# Kappa_R1.net
KiCad netlist of a schematic drawn in EAGLE
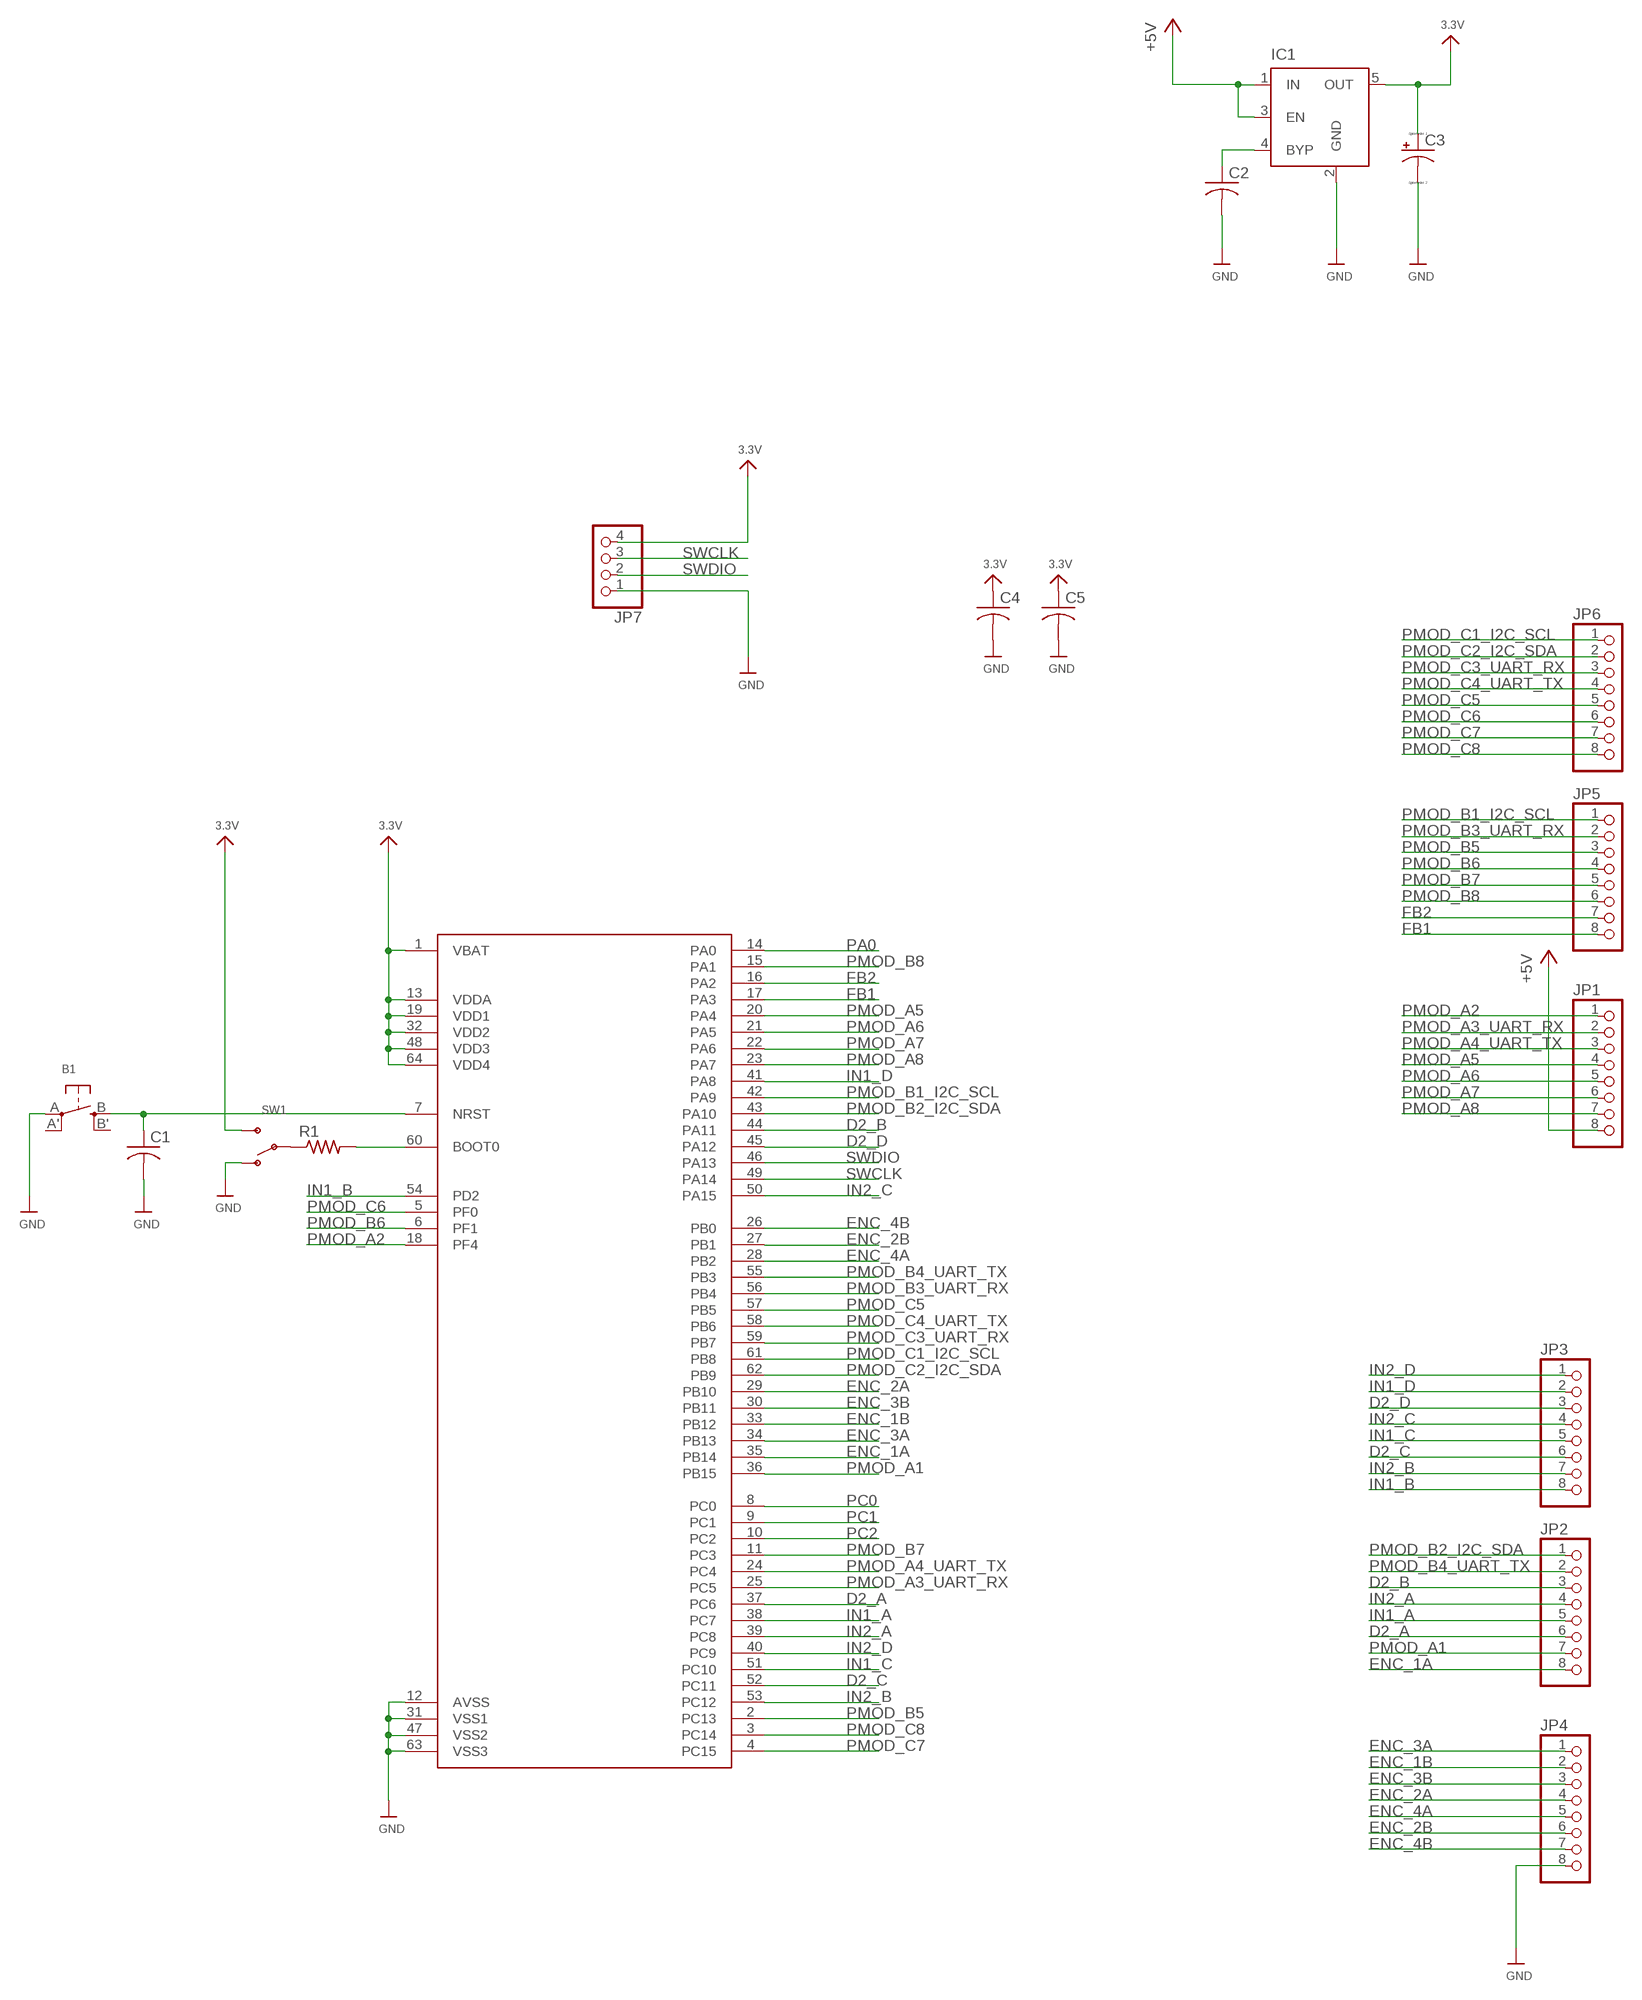
[diagram p0: schematic, sheet 1]

(export (version "E")
  (design (tool "Eeschema 10.0.6"))
  (components
    (comp (ref "B1")
      (value "SWITCH_TACT_SMT4.6X2.8")
      (footprint "eagle-import:BTN_KMR2_4.6X2.8")
      (libsource (lib "eagle-import") (part "SWITCH_TACT_SMT4.6X2.8"))
    )
    (comp (ref "C1")
      (value "C-USC0805K")
      (footprint "eagle-import:C0805K")
      (libsource (lib "eagle-import") (part "C-USC0805K"))
    )
    (comp (ref "C2")
      (value "C-USC0805K")
      (footprint "eagle-import:C0805K")
      (libsource (lib "eagle-import") (part "C-USC0805K"))
    )
    (comp (ref "C3")
      (value "CPOL-USCT3216")
      (footprint "eagle-import:CT3216")
      (libsource (lib "eagle-import") (part "CPOL-USCT3216"))
    )
    (comp (ref "C4")
      (value "C-USC0805")
      (footprint "eagle-import:C0805")
      (libsource (lib "eagle-import") (part "C-USC0805"))
    )
    (comp (ref "C5")
      (value "C-USC0805")
      (footprint "eagle-import:C0805")
      (libsource (lib "eagle-import") (part "C-USC0805"))
    )
    (comp (ref "IC1")
      (value "MIC5219XX")
      (footprint "eagle-import:SOT23-5")
      (libsource (lib "eagle-import") (part "MIC5219XX"))
    )
    (comp (ref "JP1")
      (value "HEADER-1X8ROUND")
      (footprint "eagle-import:1X08_ROUND")
      (libsource (lib "eagle-import") (part "HEADER-1X8ROUND"))
    )
    (comp (ref "JP2")
      (value "HEADER-1X8ROUND")
      (footprint "eagle-import:1X08_ROUND")
      (libsource (lib "eagle-import") (part "HEADER-1X8ROUND"))
    )
    (comp (ref "JP3")
      (value "HEADER-1X8ROUND")
      (footprint "eagle-import:1X08_ROUND")
      (libsource (lib "eagle-import") (part "HEADER-1X8ROUND"))
    )
    (comp (ref "JP4")
      (value "HEADER-1X8ROUND")
      (footprint "eagle-import:1X08_ROUND")
      (libsource (lib "eagle-import") (part "HEADER-1X8ROUND"))
    )
    (comp (ref "JP5")
      (value "HEADER-1X8ROUND")
      (footprint "eagle-import:1X08_ROUND")
      (libsource (lib "eagle-import") (part "HEADER-1X8ROUND"))
    )
    (comp (ref "JP6")
      (value "HEADER-1X8ROUND")
      (footprint "eagle-import:1X08_ROUND")
      (libsource (lib "eagle-import") (part "HEADER-1X8ROUND"))
    )
    (comp (ref "JP7")
      (value "HEADER-1X4ROUND")
      (footprint "eagle-import:1X04_ROUND")
      (libsource (lib "eagle-import") (part "HEADER-1X4ROUND"))
    )
    (comp (ref "R1")
      (value "R-US_R0805")
      (footprint "eagle-import:R0805")
      (libsource (lib "eagle-import") (part "R-US_R0805"))
    )
    (comp (ref "SW1")
      (value "SWITCH_SPDT")
      (footprint "eagle-import:SPDT_SMT_SSSS811101")
      (libsource (lib "eagle-import") (part "SWITCH_SPDT"))
    )
    (comp (ref "U$1")
      (value "STM32F303")
      (footprint "eagle-import:LQFP64")
      (libsource (lib "eagle-import") (part "STM32F303"))
    )
  )
  (nets
    (net (code "1") (name "+5V") (class "Default")
      (node (ref "IC1") (pin "1") (pinfunction "IN_1") (pintype "input"))
      (node (ref "IC1") (pin "3") (pinfunction "EN_3") (pintype "input"))
      (node (ref "JP1") (pin "8") (pinfunction "8_8") (pintype "passive"))
    )
    (net (code "2") (name "3.3V") (class "Default")
      (node (ref "C3") (pin "-") (pinfunction "+_-") (pintype "passive"))
      (node (ref "C4") (pin "1") (pinfunction "1_1") (pintype "passive"))
      (node (ref "C5") (pin "1") (pinfunction "1_1") (pintype "passive"))
      (node (ref "IC1") (pin "5") (pinfunction "OUT_5") (pintype "output"))
      (node (ref "JP7") (pin "4") (pinfunction "4_4") (pintype "passive"))
      (node (ref "SW1") (pin "C") (pinfunction "S_C") (pintype "passive"))
      (node (ref "U$1") (pin "1") (pinfunction "VBAT_1") (pintype "power_in"))
      (node (ref "U$1") (pin "13") (pinfunction "VDDA_13") (pintype "power_in"))
      (node (ref "U$1") (pin "19") (pinfunction "VDD1_19") (pintype "power_in"))
      (node (ref "U$1") (pin "32") (pinfunction "VDD2_32") (pintype "power_in"))
      (node (ref "U$1") (pin "48") (pinfunction "VDD3_48") (pintype "power_in"))
      (node (ref "U$1") (pin "64") (pinfunction "VDD4_64") (pintype "power_in"))
    )
    (net (code "3") (name "D2_A") (class "Default")
      (node (ref "JP2") (pin "6") (pinfunction "6_6") (pintype "passive"))
      (node (ref "U$1") (pin "37") (pinfunction "PC6_37") (pintype "bidirectional"))
    )
    (net (code "4") (name "D2_B") (class "Default")
      (node (ref "JP2") (pin "3") (pinfunction "3_3") (pintype "passive"))
      (node (ref "U$1") (pin "44") (pinfunction "PA11_44") (pintype "bidirectional"))
    )
    (net (code "5") (name "D2_C") (class "Default")
      (node (ref "JP3") (pin "6") (pinfunction "6_6") (pintype "passive"))
      (node (ref "U$1") (pin "52") (pinfunction "PC11_52") (pintype "bidirectional"))
    )
    (net (code "6") (name "D2_D") (class "Default")
      (node (ref "JP3") (pin "3") (pinfunction "3_3") (pintype "passive"))
      (node (ref "U$1") (pin "45") (pinfunction "PA12_45") (pintype "bidirectional"))
    )
    (net (code "7") (name "ENC_1A") (class "Default")
      (node (ref "JP2") (pin "8") (pinfunction "8_8") (pintype "passive"))
      (node (ref "U$1") (pin "35") (pinfunction "PB14_35") (pintype "bidirectional"))
    )
    (net (code "8") (name "ENC_1B") (class "Default")
      (node (ref "JP4") (pin "2") (pinfunction "2_2") (pintype "passive"))
      (node (ref "U$1") (pin "33") (pinfunction "PB12_33") (pintype "bidirectional"))
    )
    (net (code "9") (name "ENC_2A") (class "Default")
      (node (ref "JP4") (pin "4") (pinfunction "4_4") (pintype "passive"))
      (node (ref "U$1") (pin "29") (pinfunction "PB10_29") (pintype "bidirectional"))
    )
    (net (code "10") (name "ENC_2B") (class "Default")
      (node (ref "JP4") (pin "6") (pinfunction "6_6") (pintype "passive"))
      (node (ref "U$1") (pin "27") (pinfunction "PB1_27") (pintype "bidirectional"))
    )
    (net (code "11") (name "ENC_3A") (class "Default")
      (node (ref "JP4") (pin "1") (pinfunction "1_1") (pintype "passive"))
      (node (ref "U$1") (pin "34") (pinfunction "PB13_34") (pintype "bidirectional"))
    )
    (net (code "12") (name "ENC_3B") (class "Default")
      (node (ref "JP4") (pin "3") (pinfunction "3_3") (pintype "passive"))
      (node (ref "U$1") (pin "30") (pinfunction "PB11_30") (pintype "bidirectional"))
    )
    (net (code "13") (name "ENC_4A") (class "Default")
      (node (ref "JP4") (pin "5") (pinfunction "5_5") (pintype "passive"))
      (node (ref "U$1") (pin "28") (pinfunction "PB2_28") (pintype "bidirectional"))
    )
    (net (code "14") (name "ENC_4B") (class "Default")
      (node (ref "JP4") (pin "7") (pinfunction "7_7") (pintype "passive"))
      (node (ref "U$1") (pin "26") (pinfunction "PB0_26") (pintype "bidirectional"))
    )
    (net (code "15") (name "FB1") (class "Default")
      (node (ref "JP5") (pin "8") (pinfunction "8_8") (pintype "passive"))
      (node (ref "U$1") (pin "17") (pinfunction "PA3_17") (pintype "bidirectional"))
    )
    (net (code "16") (name "FB2") (class "Default")
      (node (ref "JP5") (pin "7") (pinfunction "7_7") (pintype "passive"))
      (node (ref "U$1") (pin "16") (pinfunction "PA2_16") (pintype "bidirectional"))
    )
    (net (code "17") (name "GND") (class "Default")
      (node (ref "B1") (pin "A") (pinfunction "P_A") (pintype "passive"))
      (node (ref "C1") (pin "2") (pinfunction "2_2") (pintype "passive"))
      (node (ref "C2") (pin "2") (pinfunction "2_2") (pintype "passive"))
      (node (ref "C3") (pin "+") (pinfunction "-_+") (pintype "passive"))
      (node (ref "C4") (pin "2") (pinfunction "2_2") (pintype "passive"))
      (node (ref "C5") (pin "2") (pinfunction "2_2") (pintype "passive"))
      (node (ref "IC1") (pin "2") (pinfunction "GND_2") (pintype "power_in"))
      (node (ref "JP4") (pin "8") (pinfunction "8_8") (pintype "passive"))
      (node (ref "JP7") (pin "1") (pinfunction "1_1") (pintype "passive"))
      (node (ref "SW1") (pin "A") (pinfunction "O_A") (pintype "passive"))
      (node (ref "U$1") (pin "12") (pinfunction "AVSS_12") (pintype "power_in"))
      (node (ref "U$1") (pin "31") (pinfunction "VSS1_31") (pintype "power_in"))
      (node (ref "U$1") (pin "47") (pinfunction "VSS2_47") (pintype "power_in"))
      (node (ref "U$1") (pin "63") (pinfunction "VSS3_63") (pintype "power_in"))
    )
    (net (code "18") (name "IN1_A") (class "Default")
      (node (ref "JP2") (pin "5") (pinfunction "5_5") (pintype "passive"))
      (node (ref "U$1") (pin "38") (pinfunction "PC7_38") (pintype "bidirectional"))
    )
    (net (code "19") (name "IN1_B") (class "Default")
      (node (ref "JP3") (pin "8") (pinfunction "8_8") (pintype "passive"))
      (node (ref "U$1") (pin "54") (pinfunction "PD2_54") (pintype "bidirectional"))
    )
    (net (code "20") (name "IN1_C") (class "Default")
      (node (ref "JP3") (pin "5") (pinfunction "5_5") (pintype "passive"))
      (node (ref "U$1") (pin "51") (pinfunction "PC10_51") (pintype "bidirectional"))
    )
    (net (code "21") (name "IN1_D") (class "Default")
      (node (ref "JP3") (pin "2") (pinfunction "2_2") (pintype "passive"))
      (node (ref "U$1") (pin "41") (pinfunction "PA8_41") (pintype "bidirectional"))
    )
    (net (code "22") (name "IN2_A") (class "Default")
      (node (ref "JP2") (pin "4") (pinfunction "4_4") (pintype "passive"))
      (node (ref "U$1") (pin "39") (pinfunction "PC8_39") (pintype "bidirectional"))
    )
    (net (code "23") (name "IN2_B") (class "Default")
      (node (ref "JP3") (pin "7") (pinfunction "7_7") (pintype "passive"))
      (node (ref "U$1") (pin "53") (pinfunction "PC12_53") (pintype "bidirectional"))
    )
    (net (code "24") (name "IN2_C") (class "Default")
      (node (ref "JP3") (pin "4") (pinfunction "4_4") (pintype "passive"))
      (node (ref "U$1") (pin "50") (pinfunction "PA15_50") (pintype "bidirectional"))
    )
    (net (code "25") (name "IN2_D") (class "Default")
      (node (ref "JP3") (pin "1") (pinfunction "1_1") (pintype "passive"))
      (node (ref "U$1") (pin "40") (pinfunction "PC9_40") (pintype "bidirectional"))
    )
    (net (code "26") (name "Net-(B1-S)") (class "Default")
      (node (ref "B1") (pin "B") (pinfunction "S_B") (pintype "passive"))
      (node (ref "C1") (pin "1") (pinfunction "1_1") (pintype "passive"))
      (node (ref "U$1") (pin "7") (pinfunction "NRST_7") (pintype "power_in"))
    )
    (net (code "27") (name "Net-(IC1-BYP)") (class "Default")
      (node (ref "C2") (pin "1") (pinfunction "1_1") (pintype "passive"))
      (node (ref "IC1") (pin "4") (pinfunction "BYP_4") (pintype "passive"))
    )
    (net (code "28") (name "Net-(SW1-P)") (class "Default")
      (node (ref "R1") (pin "1") (pinfunction "1_1") (pintype "passive"))
      (node (ref "SW1") (pin "B") (pinfunction "P_B") (pintype "passive"))
    )
    (net (code "29") (name "Net-(U$1-BOOT0)") (class "Default")
      (node (ref "R1") (pin "2") (pinfunction "2_2") (pintype "passive"))
      (node (ref "U$1") (pin "60") (pinfunction "BOOT0_60") (pintype "power_in"))
    )
    (net (code "30") (name "PA0") (class "Default")
      (node (ref "U$1") (pin "14") (pinfunction "PA0_14") (pintype "bidirectional"))
    )
    (net (code "31") (name "PC0") (class "Default")
      (node (ref "U$1") (pin "8") (pinfunction "PC0_8") (pintype "bidirectional"))
    )
    (net (code "32") (name "PC1") (class "Default")
      (node (ref "U$1") (pin "9") (pinfunction "PC1_9") (pintype "bidirectional"))
    )
    (net (code "33") (name "PC2") (class "Default")
      (node (ref "U$1") (pin "10") (pinfunction "PC2_10") (pintype "bidirectional"))
    )
    (net (code "34") (name "PMOD_A1") (class "Default")
      (node (ref "JP2") (pin "7") (pinfunction "7_7") (pintype "passive"))
      (node (ref "U$1") (pin "36") (pinfunction "PB15_36") (pintype "bidirectional"))
    )
    (net (code "35") (name "PMOD_A2") (class "Default")
      (node (ref "JP1") (pin "1") (pinfunction "1_1") (pintype "passive"))
      (node (ref "U$1") (pin "18") (pinfunction "PF4_18") (pintype "bidirectional"))
    )
    (net (code "36") (name "PMOD_A3_UART_RX") (class "Default")
      (node (ref "JP1") (pin "2") (pinfunction "2_2") (pintype "passive"))
      (node (ref "U$1") (pin "25") (pinfunction "PC5_25") (pintype "bidirectional"))
    )
    (net (code "37") (name "PMOD_A4_UART_TX") (class "Default")
      (node (ref "JP1") (pin "3") (pinfunction "3_3") (pintype "passive"))
      (node (ref "U$1") (pin "24") (pinfunction "PC4_24") (pintype "bidirectional"))
    )
    (net (code "38") (name "PMOD_A5") (class "Default")
      (node (ref "JP1") (pin "4") (pinfunction "4_4") (pintype "passive"))
      (node (ref "U$1") (pin "20") (pinfunction "PA4_20") (pintype "bidirectional"))
    )
    (net (code "39") (name "PMOD_A6") (class "Default")
      (node (ref "JP1") (pin "5") (pinfunction "5_5") (pintype "passive"))
      (node (ref "U$1") (pin "21") (pinfunction "PA5_21") (pintype "bidirectional"))
    )
    (net (code "40") (name "PMOD_A7") (class "Default")
      (node (ref "JP1") (pin "6") (pinfunction "6_6") (pintype "passive"))
      (node (ref "U$1") (pin "22") (pinfunction "PA6_22") (pintype "bidirectional"))
    )
    (net (code "41") (name "PMOD_A8") (class "Default")
      (node (ref "JP1") (pin "7") (pinfunction "7_7") (pintype "passive"))
      (node (ref "U$1") (pin "23") (pinfunction "PA7_23") (pintype "bidirectional"))
    )
    (net (code "42") (name "PMOD_B1_I2C_SCL") (class "Default")
      (node (ref "JP5") (pin "1") (pinfunction "1_1") (pintype "passive"))
      (node (ref "U$1") (pin "42") (pinfunction "PA9_42") (pintype "bidirectional"))
    )
    (net (code "43") (name "PMOD_B2_I2C_SDA") (class "Default")
      (node (ref "JP2") (pin "1") (pinfunction "1_1") (pintype "passive"))
      (node (ref "U$1") (pin "43") (pinfunction "PA10_43") (pintype "bidirectional"))
    )
    (net (code "44") (name "PMOD_B3_UART_RX") (class "Default")
      (node (ref "JP5") (pin "2") (pinfunction "2_2") (pintype "passive"))
      (node (ref "U$1") (pin "56") (pinfunction "PB4_56") (pintype "bidirectional"))
    )
    (net (code "45") (name "PMOD_B4_UART_TX") (class "Default")
      (node (ref "JP2") (pin "2") (pinfunction "2_2") (pintype "passive"))
      (node (ref "U$1") (pin "55") (pinfunction "PB3_55") (pintype "bidirectional"))
    )
    (net (code "46") (name "PMOD_B5") (class "Default")
      (node (ref "JP5") (pin "3") (pinfunction "3_3") (pintype "passive"))
      (node (ref "U$1") (pin "2") (pinfunction "PC13_2") (pintype "bidirectional"))
    )
    (net (code "47") (name "PMOD_B6") (class "Default")
      (node (ref "JP5") (pin "4") (pinfunction "4_4") (pintype "passive"))
      (node (ref "U$1") (pin "6") (pinfunction "PF1_6") (pintype "bidirectional"))
    )
    (net (code "48") (name "PMOD_B7") (class "Default")
      (node (ref "JP5") (pin "5") (pinfunction "5_5") (pintype "passive"))
      (node (ref "U$1") (pin "11") (pinfunction "PC3_11") (pintype "bidirectional"))
    )
    (net (code "49") (name "PMOD_B8") (class "Default")
      (node (ref "JP5") (pin "6") (pinfunction "6_6") (pintype "passive"))
      (node (ref "U$1") (pin "15") (pinfunction "PA1_15") (pintype "bidirectional"))
    )
    (net (code "50") (name "PMOD_C1_I2C_SCL") (class "Default")
      (node (ref "JP6") (pin "1") (pinfunction "1_1") (pintype "passive"))
      (node (ref "U$1") (pin "61") (pinfunction "PB8_61") (pintype "bidirectional"))
    )
    (net (code "51") (name "PMOD_C2_I2C_SDA") (class "Default")
      (node (ref "JP6") (pin "2") (pinfunction "2_2") (pintype "passive"))
      (node (ref "U$1") (pin "62") (pinfunction "PB9_62") (pintype "bidirectional"))
    )
    (net (code "52") (name "PMOD_C3_UART_RX") (class "Default")
      (node (ref "JP6") (pin "3") (pinfunction "3_3") (pintype "passive"))
      (node (ref "U$1") (pin "59") (pinfunction "PB7_59") (pintype "bidirectional"))
    )
    (net (code "53") (name "PMOD_C4_UART_TX") (class "Default")
      (node (ref "JP6") (pin "4") (pinfunction "4_4") (pintype "passive"))
      (node (ref "U$1") (pin "58") (pinfunction "PB6_58") (pintype "bidirectional"))
    )
    (net (code "54") (name "PMOD_C5") (class "Default")
      (node (ref "JP6") (pin "5") (pinfunction "5_5") (pintype "passive"))
      (node (ref "U$1") (pin "57") (pinfunction "PB5_57") (pintype "bidirectional"))
    )
    (net (code "55") (name "PMOD_C6") (class "Default")
      (node (ref "JP6") (pin "6") (pinfunction "6_6") (pintype "passive"))
      (node (ref "U$1") (pin "5") (pinfunction "PF0_5") (pintype "bidirectional"))
    )
    (net (code "56") (name "PMOD_C7") (class "Default")
      (node (ref "JP6") (pin "7") (pinfunction "7_7") (pintype "passive"))
      (node (ref "U$1") (pin "4") (pinfunction "PC15_4") (pintype "bidirectional"))
    )
    (net (code "57") (name "PMOD_C8") (class "Default")
      (node (ref "JP6") (pin "8") (pinfunction "8_8") (pintype "passive"))
      (node (ref "U$1") (pin "3") (pinfunction "PC14_3") (pintype "bidirectional"))
    )
    (net (code "58") (name "SWCLK") (class "Default")
      (node (ref "JP7") (pin "3") (pinfunction "3_3") (pintype "passive"))
      (node (ref "U$1") (pin "49") (pinfunction "PA14_49") (pintype "bidirectional"))
    )
    (net (code "59") (name "SWDIO") (class "Default")
      (node (ref "JP7") (pin "2") (pinfunction "2_2") (pintype "passive"))
      (node (ref "U$1") (pin "46") (pinfunction "PA13_46") (pintype "bidirectional"))
    )
    (net (code "60") (name "unconnected-(B1-P1-PadA')") (class "Default")
      (node (ref "B1") (pin "A'") (pinfunction "P1_A'") (pintype "passive"))
    )
    (net (code "61") (name "unconnected-(B1-S1-PadB')") (class "Default")
      (node (ref "B1") (pin "B'") (pinfunction "S1_B'") (pintype "passive"))
    )
  )
)
